# Program_Interface.net
KiCad netlist of a schematic drawn in Altium Designer
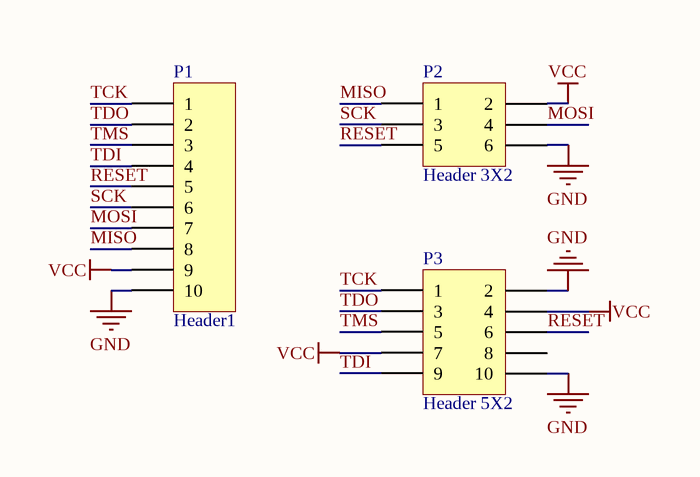
[diagram p0: Program_Interface.SchDoc]

(export (version "E")
  (design (tool "Eeschema 10.0.6"))
  (components
    (comp (ref "P1")
      (value "Header1")
      (footprint "HDR1X10H")
      (description "Header, 10-Pin")
      (fields (field (name "PUBLISHER") "Altium Limited"))
      (libsource (lib "Miscellaneous Connectors") (part "Header 10"))
    )
    (comp (ref "P2")
      (value "Header 3X2")
      (footprint "HDR2X3")
      (description "Header, 3-Pin, Dual row")
      (fields (field (name "PUBLISHER") "Altium Limited"))
      (libsource (lib "Miscellaneous Connectors") (part "Header 3X2"))
    )
    (comp (ref "P3")
      (value "Header 5X2")
      (footprint "HDR2X5")
      (description "Header, 5-Pin, Dual row")
      (fields (field (name "PUBLISHER") "Altium Limited"))
      (libsource (lib "Miscellaneous Connectors") (part "Header 5X2"))
    )
  )
  (nets
    (net (code "1") (name "/MISO") (class "Default")
      (node (ref "P1") (pin "8") (pinfunction "8_8") (pintype "passive"))
      (node (ref "P2") (pin "1") (pinfunction "1_1") (pintype "passive"))
    )
    (net (code "2") (name "/MOSI") (class "Default")
      (node (ref "P1") (pin "7") (pinfunction "7_7") (pintype "passive"))
      (node (ref "P2") (pin "4") (pinfunction "4_4") (pintype "passive"))
    )
    (net (code "3") (name "/RESET") (class "Default")
      (node (ref "P1") (pin "5") (pinfunction "5_5") (pintype "passive"))
      (node (ref "P2") (pin "5") (pinfunction "5_5") (pintype "passive"))
      (node (ref "P3") (pin "6") (pinfunction "6_6") (pintype "passive"))
    )
    (net (code "4") (name "/SCK") (class "Default")
      (node (ref "P1") (pin "6") (pinfunction "6_6") (pintype "passive"))
      (node (ref "P2") (pin "3") (pinfunction "3_3") (pintype "passive"))
    )
    (net (code "5") (name "/TCK") (class "Default")
      (node (ref "P1") (pin "1") (pinfunction "1_1") (pintype "passive"))
      (node (ref "P3") (pin "1") (pinfunction "1_1") (pintype "passive"))
    )
    (net (code "6") (name "/TDI") (class "Default")
      (node (ref "P1") (pin "4") (pinfunction "4_4") (pintype "passive"))
      (node (ref "P3") (pin "9") (pinfunction "9_9") (pintype "passive"))
    )
    (net (code "7") (name "/TDO") (class "Default")
      (node (ref "P1") (pin "2") (pinfunction "2_2") (pintype "passive"))
      (node (ref "P3") (pin "3") (pinfunction "3_3") (pintype "passive"))
    )
    (net (code "8") (name "/TMS") (class "Default")
      (node (ref "P1") (pin "3") (pinfunction "3_3") (pintype "passive"))
      (node (ref "P3") (pin "5") (pinfunction "5_5") (pintype "passive"))
    )
    (net (code "9") (name "GND") (class "Default")
      (node (ref "P1") (pin "10") (pinfunction "10_10") (pintype "passive"))
      (node (ref "P2") (pin "6") (pinfunction "6_6") (pintype "passive"))
      (node (ref "P3") (pin "10") (pinfunction "10_10") (pintype "passive"))
      (node (ref "P3") (pin "2") (pinfunction "2_2") (pintype "passive"))
    )
    (net (code "10") (name "VCC") (class "Default")
      (node (ref "P1") (pin "9") (pinfunction "9_9") (pintype "passive"))
      (node (ref "P2") (pin "2") (pinfunction "2_2") (pintype "passive"))
      (node (ref "P3") (pin "4") (pinfunction "4_4") (pintype "passive"))
      (node (ref "P3") (pin "7") (pinfunction "7_7") (pintype "passive"))
    )
    (net (code "11") (name "unconnected-(P3-Pad8)") (class "Default")
      (node (ref "P3") (pin "8") (pinfunction "8_8") (pintype "passive"))
    )
  )
)
